# MCU.net
KiCad netlist of a schematic drawn in Altium Designer
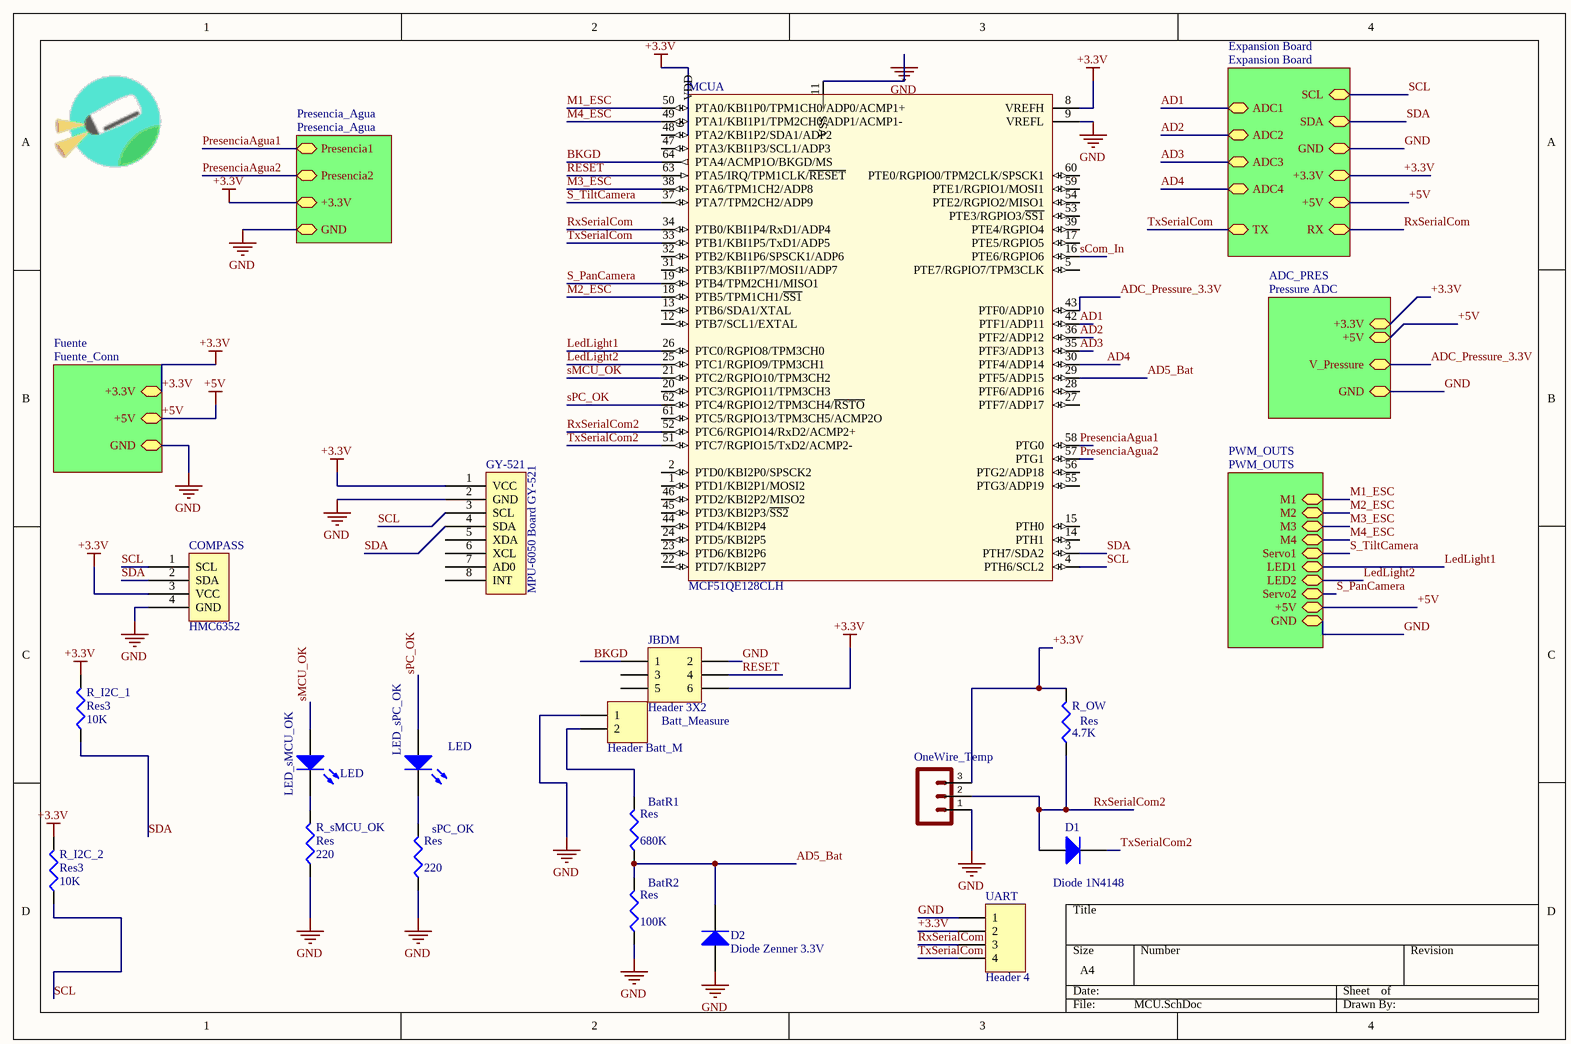
[diagram p0: MCU.SchDoc]

(export (version "E")
  (design (tool "Eeschema 10.0.6"))
  (components
    (comp (ref "BatR1")
      (value "Res")
      (footprint "6-0805_L")
      (description "Resistor")
      (fields (field (name "ALTIUM_VALUE") "680K") (field (name "PUBLISHER") "Altium Limited"))
      (libsource (lib "Miscellaneous Devices") (part "Res3"))
    )
    (comp (ref "BatR2")
      (value "Res")
      (footprint "6-0805_L")
      (description "Resistor")
      (fields (field (name "ALTIUM_VALUE") "100K") (field (name "PUBLISHER") "Altium Limited"))
      (libsource (lib "Miscellaneous Devices") (part "Res3"))
    )
    (comp (ref "Batt_Measure")
      (value "Header Batt_M")
      (footprint "5.08mm 200 mil Screw Terminal SF")
      (description "Header, 2-Pin")
      (fields (field (name "PUBLISHER") "Altium Limited"))
      (libsource (lib "Miscellaneous Connectors") (part "Header 2"))
    )
    (comp (ref "COMPASS")
      (value "HMC6352")
      (footprint "HMC6352_SF")
      (libsource (lib "XSUB_COMP") (part "HMC6352"))
    )
    (comp (ref "D1")
      (value "Diode 1N4148")
      (footprint "miniMELF")
      (description "High Conductance Fast Diode")
      (fields (field (name "PUBLISHER") "Altium Limited"))
      (libsource (lib "Miscellaneous Devices") (part "Diode 1N4148"))
    )
    (comp (ref "D2")
      (value "Diode Zenner 3.3V")
      (footprint "miniMELF")
      (description "High Conductance Fast Diode")
      (fields (field (name "PUBLISHER") "Altium Limited"))
      (libsource (lib "Miscellaneous Devices") (part "Diode 1N4148"))
    )
    (comp (ref "GY-521")
      (value "MPU-6050 Board GY-521")
      (footprint "GY-521")
      (libsource (lib "XSUB_COMP") (part "GY-521"))
    )
    (comp (ref "JBDM")
      (value "Header 3X2")
      (footprint "HDR2X3")
      (description "Header, 3-Pin, Dual row")
      (fields (field (name "PUBLISHER") "Altium Limited"))
      (libsource (lib "Miscellaneous Connectors") (part "Header 3X2"))
    )
    (comp (ref "LED_sMCU_OK")
      (value "LED")
      (footprint "6-0805_L")
      (description "Typical RED, GREEN, YELLOW, AMBER GaAs LED")
      (fields (field (name "PUBLISHER") "Altium Limited"))
      (libsource (lib "Miscellaneous Devices") (part "LED2"))
    )
    (comp (ref "LED_sPC_OK")
      (value "LED")
      (footprint "6-0805_L")
      (description "Typical RED, GREEN, YELLOW, AMBER GaAs LED")
      (fields (field (name "PUBLISHER") "Altium Limited"))
      (libsource (lib "Miscellaneous Devices") (part "LED2"))
    )
    (comp (ref "MCU")
      (value "MCF51QE128CLH")
      (footprint "840F-02_N")
      (description "MCF51QE128 ColdFire V1 Microcontroller, 32-Bit, 128KB Flash, 8KB RAM, -40°C to 85°C, 64-Pin LQFP")
      (libsource (lib "Freescale Semiconductor ColdFire MCU") (part "MCF51QE128CLH"))
    )
    (comp (ref "OneWire_Temp")
      (value "~")
      (footprint "HDR1X3")
      (libsource (lib "SparkFun-Connectors") (part "M03-SCREW-5MM"))
    )
    (comp (ref "R_I2C_1")
      (value "Res3")
      (footprint "6-0805_L")
      (description "Resistor")
      (fields (field (name "ALTIUM_VALUE") "10K") (field (name "PUBLISHER") "Altium Limited"))
      (libsource (lib "Miscellaneous Devices") (part "Res3"))
    )
    (comp (ref "R_I2C_2")
      (value "Res3")
      (footprint "6-0805_L")
      (description "Resistor")
      (fields (field (name "ALTIUM_VALUE") "10K") (field (name "PUBLISHER") "Altium Limited"))
      (libsource (lib "Miscellaneous Devices") (part "Res3"))
    )
    (comp (ref "R_OW")
      (value "Res")
      (footprint "6-0805_L")
      (description "Resistor")
      (fields (field (name "ALTIUM_VALUE") "4.7K") (field (name "PUBLISHER") "Altium Limited"))
      (libsource (lib "Miscellaneous Devices") (part "Res3"))
    )
    (comp (ref "R_sMCU_OK")
      (value "Res")
      (footprint "6-0805_L")
      (description "Resistor")
      (fields (field (name "ALTIUM_VALUE") "220") (field (name "PUBLISHER") "Altium Limited"))
      (libsource (lib "Miscellaneous Devices") (part "Res3"))
    )
    (comp (ref "sPC_OK")
      (value "Res")
      (footprint "6-0805_L")
      (description "Resistor")
      (fields (field (name "ALTIUM_VALUE") "220") (field (name "PUBLISHER") "Altium Limited"))
      (libsource (lib "Miscellaneous Devices") (part "Res3"))
    )
    (comp (ref "UART")
      (value "Header 4")
      (footprint "HDR1X4")
      (description "Header, 4-Pin")
      (fields (field (name "PUBLISHER") "Altium Limited"))
      (libsource (lib "Miscellaneous Connectors") (part "Header 4"))
    )
  )
  (nets
    (net (code "1") (name "+3.3V") (class "Default")
      (node (ref "COMPASS") (pin "3") (pinfunction "VCC_3") (pintype "passive"))
      (node (ref "GY-521") (pin "1") (pinfunction "VCC_1") (pintype "power_in"))
      (node (ref "JBDM") (pin "6") (pinfunction "6_6") (pintype "passive"))
      (node (ref "MCU") (pin "6") (pinfunction "VDD_6") (pintype "power_in"))
      (node (ref "MCU") (pin "8") (pinfunction "VREFH_8") (pintype "passive"))
      (node (ref "OneWire_Temp") (pin "3") (pinfunction "3_3") (pintype "passive"))
      (node (ref "R_I2C_1") (pin "2") (pinfunction "2_2") (pintype "passive"))
      (node (ref "R_I2C_2") (pin "2") (pinfunction "2_2") (pintype "passive"))
      (node (ref "R_OW") (pin "2") (pinfunction "2_2") (pintype "passive"))
      (node (ref "UART") (pin "2") (pinfunction "2_2") (pintype "passive"))
    )
    (net (code "3") (name "/AD1") (class "Default")
      (node (ref "MCU") (pin "42") (pinfunction "PTF1/ADP11_42") (pintype "bidirectional"))
    )
    (net (code "4") (name "/AD2") (class "Default")
      (node (ref "MCU") (pin "36") (pinfunction "PTF2/ADP12_36") (pintype "bidirectional"))
    )
    (net (code "5") (name "/AD3") (class "Default")
      (node (ref "MCU") (pin "35") (pinfunction "PTF3/ADP13_35") (pintype "bidirectional"))
    )
    (net (code "6") (name "/AD4") (class "Default")
      (node (ref "MCU") (pin "30") (pinfunction "PTF4/ADP14_30") (pintype "bidirectional"))
    )
    (net (code "7") (name "/AD5_Bat") (class "Default")
      (node (ref "BatR1") (pin "1") (pinfunction "1_1") (pintype "passive"))
      (node (ref "BatR2") (pin "2") (pinfunction "2_2") (pintype "passive"))
      (node (ref "D2") (pin "2") (pinfunction "K_2") (pintype "passive"))
      (node (ref "MCU") (pin "29") (pinfunction "PTF5/ADP15_29") (pintype "bidirectional"))
    )
    (net (code "8") (name "/ADC_Pressure_3.3V") (class "Default")
      (node (ref "MCU") (pin "43") (pinfunction "PTF0/ADP10_43") (pintype "bidirectional"))
    )
    (net (code "9") (name "/BKGD") (class "Default")
      (node (ref "JBDM") (pin "1") (pinfunction "1_1") (pintype "passive"))
      (node (ref "MCU") (pin "64") (pinfunction "PTA4/ACMP1O/BKGD/MS_64") (pintype "output"))
    )
    (net (code "10") (name "/LedLight1") (class "Default")
      (node (ref "MCU") (pin "26") (pinfunction "PTC0/RGPIO8/TPM3CH0_26") (pintype "bidirectional"))
    )
    (net (code "11") (name "/LedLight2") (class "Default")
      (node (ref "MCU") (pin "25") (pinfunction "PTC1/RGPIO9/TPM3CH1_25") (pintype "bidirectional"))
    )
    (net (code "12") (name "/M1_ESC") (class "Default")
      (node (ref "MCU") (pin "50") (pinfunction "PTA0/KBI1P0/TPM1CH0/ADP0/ACMP1+_50") (pintype "bidirectional"))
    )
    (net (code "13") (name "/M2_ESC") (class "Default")
      (node (ref "MCU") (pin "18") (pinfunction "PTB5/TPM1CH1/~{SS1}_18") (pintype "bidirectional"))
    )
    (net (code "14") (name "/M3_ESC") (class "Default")
      (node (ref "MCU") (pin "38") (pinfunction "PTA6/TPM1CH2/ADP8_38") (pintype "bidirectional"))
    )
    (net (code "15") (name "/M4_ESC") (class "Default")
      (node (ref "MCU") (pin "49") (pinfunction "PTA1/KBI1P1/TPM2CH0/ADP1/ACMP1-_49") (pintype "bidirectional"))
    )
    (net (code "16") (name "/PresenciaAgua1") (class "Default")
      (node (ref "MCU") (pin "58") (pinfunction "PTG0_58") (pintype "bidirectional"))
    )
    (net (code "17") (name "/PresenciaAgua2") (class "Default")
      (node (ref "MCU") (pin "57") (pinfunction "PTG1_57") (pintype "bidirectional"))
    )
    (net (code "18") (name "/RESET") (class "Default")
      (node (ref "JBDM") (pin "4") (pinfunction "4_4") (pintype "passive"))
      (node (ref "MCU") (pin "63") (pinfunction "PTA5/IRQ/TPM1CLK/~{RESET}_63") (pintype "input"))
    )
    (net (code "19") (name "/RxSerialCom") (class "Default")
      (node (ref "MCU") (pin "34") (pinfunction "PTB0/KBI1P4/RxD1/ADP4_34") (pintype "bidirectional"))
      (node (ref "UART") (pin "3") (pinfunction "3_3") (pintype "passive"))
    )
    (net (code "20") (name "/RxSerialCom2") (class "Default")
      (node (ref "D1") (pin "1") (pinfunction "A_1") (pintype "passive"))
      (node (ref "MCU") (pin "52") (pinfunction "PTC6/RGPIO14/RxD2/ACMP2+_52") (pintype "bidirectional"))
      (node (ref "OneWire_Temp") (pin "2") (pinfunction "2_2") (pintype "passive"))
      (node (ref "R_OW") (pin "1") (pinfunction "1_1") (pintype "passive"))
    )
    (net (code "21") (name "/SCL") (class "Default")
      (node (ref "COMPASS") (pin "1") (pinfunction "SCL_1") (pintype "passive"))
      (node (ref "GY-521") (pin "3") (pinfunction "SCL_3") (pintype "passive"))
      (node (ref "MCU") (pin "4") (pinfunction "PTH6/SCL2_4") (pintype "bidirectional"))
      (node (ref "R_I2C_2") (pin "1") (pinfunction "1_1") (pintype "passive"))
    )
    (net (code "22") (name "/SDA") (class "Default")
      (node (ref "COMPASS") (pin "2") (pinfunction "SDA_2") (pintype "passive"))
      (node (ref "GY-521") (pin "4") (pinfunction "SDA_4") (pintype "passive"))
      (node (ref "MCU") (pin "3") (pinfunction "PTH7/SDA2_3") (pintype "bidirectional"))
      (node (ref "R_I2C_1") (pin "1") (pinfunction "1_1") (pintype "passive"))
    )
    (net (code "23") (name "/S_PanCamera") (class "Default")
      (node (ref "MCU") (pin "19") (pinfunction "PTB4/TPM2CH1/MISO1_19") (pintype "bidirectional"))
    )
    (net (code "24") (name "/S_TiltCamera") (class "Default")
      (node (ref "MCU") (pin "37") (pinfunction "PTA7/TPM2CH2/ADP9_37") (pintype "bidirectional"))
    )
    (net (code "25") (name "/TxSerialCom") (class "Default")
      (node (ref "MCU") (pin "33") (pinfunction "PTB1/KBI1P5/TxD1/ADP5_33") (pintype "bidirectional"))
      (node (ref "UART") (pin "4") (pinfunction "4_4") (pintype "passive"))
    )
    (net (code "26") (name "/TxSerialCom2") (class "Default")
      (node (ref "D1") (pin "2") (pinfunction "K_2") (pintype "passive"))
      (node (ref "MCU") (pin "51") (pinfunction "PTC7/RGPIO15/TxD2/ACMP2-_51") (pintype "bidirectional"))
    )
    (net (code "27") (name "/sCom_In") (class "Default")
      (node (ref "MCU") (pin "16") (pinfunction "PTE6/RGPIO6_16") (pintype "bidirectional"))
    )
    (net (code "28") (name "/sMCU_OK") (class "Default")
      (node (ref "LED_sMCU_OK") (pin "1") (pinfunction "A_1") (pintype "passive"))
      (node (ref "MCU") (pin "21") (pinfunction "PTC2/RGPIO10/TPM3CH2_21") (pintype "bidirectional"))
    )
    (net (code "29") (name "/sPC_OK") (class "Default")
      (node (ref "LED_sPC_OK") (pin "1") (pinfunction "A_1") (pintype "passive"))
      (node (ref "MCU") (pin "62") (pinfunction "PTC4/RGPIO12/TPM3CH4/~{RSTO}_62") (pintype "bidirectional"))
    )
    (net (code "30") (name "GND") (class "Default")
      (node (ref "BatR2") (pin "1") (pinfunction "1_1") (pintype "passive"))
      (node (ref "Batt_Measure") (pin "1") (pinfunction "1_1") (pintype "passive"))
      (node (ref "COMPASS") (pin "4") (pinfunction "GND_4") (pintype "passive"))
      (node (ref "D2") (pin "1") (pinfunction "A_1") (pintype "passive"))
      (node (ref "GY-521") (pin "2") (pinfunction "GND_2") (pintype "power_in"))
      (node (ref "JBDM") (pin "2") (pinfunction "2_2") (pintype "passive"))
      (node (ref "MCU") (pin "11") (pinfunction "VSS_11") (pintype "power_in"))
      (node (ref "MCU") (pin "9") (pinfunction "VREFL_9") (pintype "passive"))
      (node (ref "OneWire_Temp") (pin "1") (pinfunction "1_1") (pintype "passive"))
      (node (ref "R_sMCU_OK") (pin "1") (pinfunction "1_1") (pintype "passive"))
      (node (ref "UART") (pin "1") (pinfunction "1_1") (pintype "passive"))
      (node (ref "sPC_OK") (pin "1") (pinfunction "1_1") (pintype "passive"))
    )
    (net (code "31") (name "Net-(BatR1-Pad2)") (class "Default")
      (node (ref "BatR1") (pin "2") (pinfunction "2_2") (pintype "passive"))
      (node (ref "Batt_Measure") (pin "2") (pinfunction "2_2") (pintype "passive"))
    )
    (net (code "32") (name "Net-(LED_sMCU_OK-K)") (class "Default")
      (node (ref "LED_sMCU_OK") (pin "2") (pinfunction "K_2") (pintype "passive"))
      (node (ref "R_sMCU_OK") (pin "2") (pinfunction "2_2") (pintype "passive"))
    )
    (net (code "33") (name "Net-(LED_sPC_OK-K)") (class "Default")
      (node (ref "LED_sPC_OK") (pin "2") (pinfunction "K_2") (pintype "passive"))
      (node (ref "sPC_OK") (pin "2") (pinfunction "2_2") (pintype "passive"))
    )
    (net (code "34") (name "unconnected-(GY-521-AD0-Pad7)") (class "Default")
      (node (ref "GY-521") (pin "7") (pinfunction "AD0_7") (pintype "passive"))
    )
    (net (code "35") (name "unconnected-(GY-521-INT-Pad8)") (class "Default")
      (node (ref "GY-521") (pin "8") (pinfunction "INT_8") (pintype "passive"))
    )
    (net (code "36") (name "unconnected-(GY-521-XCL-Pad6)") (class "Default")
      (node (ref "GY-521") (pin "6") (pinfunction "XCL_6") (pintype "passive"))
    )
    (net (code "37") (name "unconnected-(GY-521-XDA-Pad5)") (class "Default")
      (node (ref "GY-521") (pin "5") (pinfunction "XDA_5") (pintype "passive"))
    )
    (net (code "38") (name "unconnected-(JBDM-Pad3)") (class "Default")
      (node (ref "JBDM") (pin "3") (pinfunction "3_3") (pintype "passive"))
    )
    (net (code "39") (name "unconnected-(JBDM-Pad5)") (class "Default")
      (node (ref "JBDM") (pin "5") (pinfunction "5_5") (pintype "passive"))
    )
    (net (code "40") (name "unconnected-(MCUA-PTA2{slash}KBI1P2{slash}SDA1{slash}ADP2-Pad48)") (class "Default")
      (node (ref "MCU") (pin "48") (pinfunction "PTA2/KBI1P2/SDA1/ADP2_48") (pintype "bidirectional"))
    )
    (net (code "41") (name "unconnected-(MCUA-PTA3{slash}KBI1P3{slash}SCL1{slash}ADP3-Pad47)") (class "Default")
      (node (ref "MCU") (pin "47") (pinfunction "PTA3/KBI1P3/SCL1/ADP3_47") (pintype "bidirectional"))
    )
    (net (code "42") (name "unconnected-(MCUA-PTB2{slash}KBI1P6{slash}SPSCK1{slash}ADP6-Pad32)") (class "Default")
      (node (ref "MCU") (pin "32") (pinfunction "PTB2/KBI1P6/SPSCK1/ADP6_32") (pintype "bidirectional"))
    )
    (net (code "43") (name "unconnected-(MCUA-PTB3{slash}KBI1P7{slash}MOSI1{slash}ADP7-Pad31)") (class "Default")
      (node (ref "MCU") (pin "31") (pinfunction "PTB3/KBI1P7/MOSI1/ADP7_31") (pintype "bidirectional"))
    )
    (net (code "44") (name "unconnected-(MCUA-PTB6{slash}SDA1{slash}XTAL-Pad13)") (class "Default")
      (node (ref "MCU") (pin "13") (pinfunction "PTB6/SDA1/XTAL_13") (pintype "bidirectional"))
    )
    (net (code "45") (name "unconnected-(MCUA-PTB7{slash}SCL1{slash}EXTAL-Pad12)") (class "Default")
      (node (ref "MCU") (pin "12") (pinfunction "PTB7/SCL1/EXTAL_12") (pintype "bidirectional"))
    )
    (net (code "46") (name "unconnected-(MCUA-PTC3{slash}RGPIO11{slash}TPM3CH3-Pad20)") (class "Default")
      (node (ref "MCU") (pin "20") (pinfunction "PTC3/RGPIO11/TPM3CH3_20") (pintype "bidirectional"))
    )
    (net (code "47") (name "unconnected-(MCUA-PTC5{slash}RGPIO13{slash}TPM3CH5{slash}ACMP2O-Pad61)") (class "Default")
      (node (ref "MCU") (pin "61") (pinfunction "PTC5/RGPIO13/TPM3CH5/ACMP2O_61") (pintype "bidirectional"))
    )
    (net (code "48") (name "unconnected-(MCUA-PTD0{slash}KBI2P0{slash}SPSCK2-Pad2)") (class "Default")
      (node (ref "MCU") (pin "2") (pinfunction "PTD0/KBI2P0/SPSCK2_2") (pintype "bidirectional"))
    )
    (net (code "49") (name "unconnected-(MCUA-PTD1{slash}KBI2P1{slash}MOSI2-Pad1)") (class "Default")
      (node (ref "MCU") (pin "1") (pinfunction "PTD1/KBI2P1/MOSI2_1") (pintype "bidirectional"))
    )
    (net (code "50") (name "unconnected-(MCUA-PTD2{slash}KBI2P2{slash}MISO2-Pad46)") (class "Default")
      (node (ref "MCU") (pin "46") (pinfunction "PTD2/KBI2P2/MISO2_46") (pintype "bidirectional"))
    )
    (net (code "51") (name "unconnected-(MCUA-PTD3{slash}KBI2P3{slash}~{SS2}-Pad45)") (class "Default")
      (node (ref "MCU") (pin "45") (pinfunction "PTD3/KBI2P3/~{SS2}_45") (pintype "bidirectional"))
    )
    (net (code "52") (name "unconnected-(MCUA-PTD4{slash}KBI2P4-Pad44)") (class "Default")
      (node (ref "MCU") (pin "44") (pinfunction "PTD4/KBI2P4_44") (pintype "bidirectional"))
    )
    (net (code "53") (name "unconnected-(MCUA-PTD5{slash}KBI2P5-Pad24)") (class "Default")
      (node (ref "MCU") (pin "24") (pinfunction "PTD5/KBI2P5_24") (pintype "bidirectional"))
    )
    (net (code "54") (name "unconnected-(MCUA-PTD6{slash}KBI2P6-Pad23)") (class "Default")
      (node (ref "MCU") (pin "23") (pinfunction "PTD6/KBI2P6_23") (pintype "bidirectional"))
    )
    (net (code "55") (name "unconnected-(MCUA-PTD7{slash}KBI2P7-Pad22)") (class "Default")
      (node (ref "MCU") (pin "22") (pinfunction "PTD7/KBI2P7_22") (pintype "bidirectional"))
    )
    (net (code "56") (name "unconnected-(MCUA-PTE0{slash}RGPIO0{slash}TPM2CLK{slash}SPSCK1-Pad60)") (class "Default")
      (node (ref "MCU") (pin "60") (pinfunction "PTE0/RGPIO0/TPM2CLK/SPSCK1_60") (pintype "bidirectional"))
    )
    (net (code "57") (name "unconnected-(MCUA-PTE1{slash}RGPIO1{slash}MOSI1-Pad59)") (class "Default")
      (node (ref "MCU") (pin "59") (pinfunction "PTE1/RGPIO1/MOSI1_59") (pintype "bidirectional"))
    )
    (net (code "58") (name "unconnected-(MCUA-PTE2{slash}RGPIO2{slash}MISO1-Pad54)") (class "Default")
      (node (ref "MCU") (pin "54") (pinfunction "PTE2/RGPIO2/MISO1_54") (pintype "bidirectional"))
    )
    (net (code "59") (name "unconnected-(MCUA-PTE3{slash}RGPIO3{slash}~{SS1}-Pad53)") (class "Default")
      (node (ref "MCU") (pin "53") (pinfunction "PTE3/RGPIO3/~{SS1}_53") (pintype "bidirectional"))
    )
    (net (code "60") (name "unconnected-(MCUA-PTE4{slash}RGPIO4-Pad39)") (class "Default")
      (node (ref "MCU") (pin "39") (pinfunction "PTE4/RGPIO4_39") (pintype "bidirectional"))
    )
    (net (code "61") (name "unconnected-(MCUA-PTE5{slash}RGPIO5-Pad17)") (class "Default")
      (node (ref "MCU") (pin "17") (pinfunction "PTE5/RGPIO5_17") (pintype "bidirectional"))
    )
    (net (code "62") (name "unconnected-(MCUA-PTE7{slash}RGPIO7{slash}TPM3CLK-Pad5)") (class "Default")
      (node (ref "MCU") (pin "5") (pinfunction "PTE7/RGPIO7/TPM3CLK_5") (pintype "bidirectional"))
    )
    (net (code "63") (name "unconnected-(MCUA-PTF6{slash}ADP16-Pad28)") (class "Default")
      (node (ref "MCU") (pin "28") (pinfunction "PTF6/ADP16_28") (pintype "bidirectional"))
    )
    (net (code "64") (name "unconnected-(MCUA-PTF7{slash}ADP17-Pad27)") (class "Default")
      (node (ref "MCU") (pin "27") (pinfunction "PTF7/ADP17_27") (pintype "bidirectional"))
    )
    (net (code "65") (name "unconnected-(MCUA-PTG2{slash}ADP18-Pad56)") (class "Default")
      (node (ref "MCU") (pin "56") (pinfunction "PTG2/ADP18_56") (pintype "bidirectional"))
    )
    (net (code "66") (name "unconnected-(MCUA-PTG3{slash}ADP19-Pad55)") (class "Default")
      (node (ref "MCU") (pin "55") (pinfunction "PTG3/ADP19_55") (pintype "bidirectional"))
    )
    (net (code "67") (name "unconnected-(MCUA-PTH0-Pad15)") (class "Default")
      (node (ref "MCU") (pin "15") (pinfunction "PTH0_15") (pintype "bidirectional"))
    )
    (net (code "68") (name "unconnected-(MCUA-PTH1-Pad14)") (class "Default")
      (node (ref "MCU") (pin "14") (pinfunction "PTH1_14") (pintype "bidirectional"))
    )
  )
)
